# dcdr_3_1.net
KiCad netlist of a schematic drawn in EAGLE
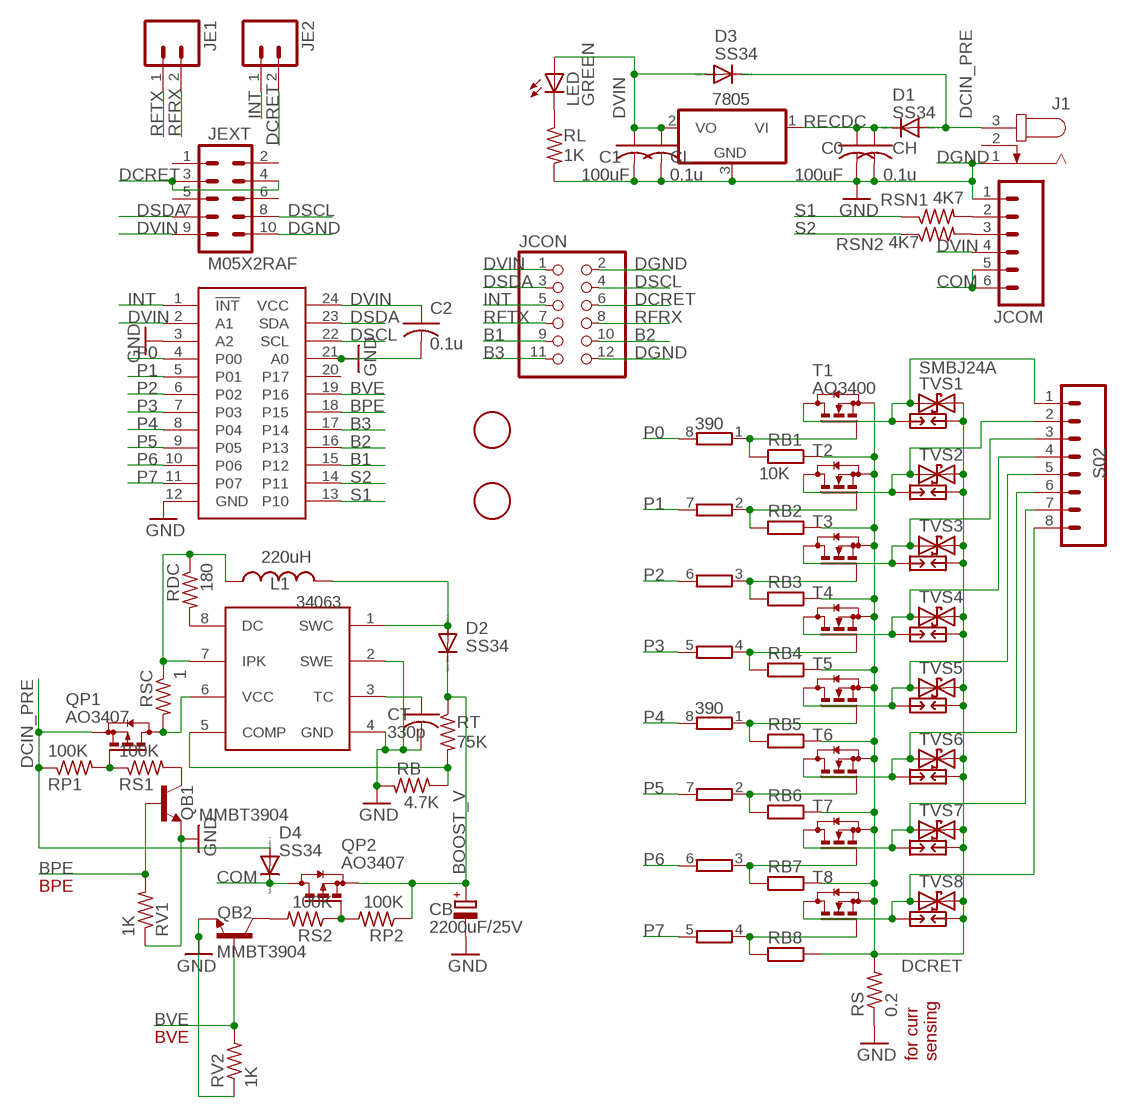
[diagram p0: schematic, sheet 1]

(export (version "E")
  (design (tool "Eeschema 10.0.6"))
  (components
    (comp (ref "7805")
      (value "7805DT")
      (footprint "eagle-import:TO252")
      (libsource (lib "eagle-import") (part "78DT05"))
    )
    (comp (ref "34063")
      (value "MC34063")
      (footprint "eagle-import:SO08")
      (libsource (lib "eagle-import") (part "MC33063/MC34063D"))
    )
    (comp (ref "C0")
      (value "100uF")
      (footprint "eagle-import:C0805K")
      (libsource (lib "eagle-import") (part "C-USC0805K"))
    )
    (comp (ref "C1")
      (value "100uF")
      (footprint "eagle-import:C0805K")
      (libsource (lib "eagle-import") (part "C-USC0805K"))
    )
    (comp (ref "C2")
      (value "0.1u")
      (footprint "eagle-import:C0603")
      (libsource (lib "eagle-import") (part "C-USC0603"))
    )
    (comp (ref "CB")
      (value "2200uF/25V")
      (footprint "eagle-import:E7,5-16")
      (libsource (lib "eagle-import") (part "CPOL-EUE7.5-16"))
    )
    (comp (ref "CH")
      (value "0.1u")
      (footprint "eagle-import:C0603")
      (libsource (lib "eagle-import") (part "C-USC0603"))
    )
    (comp (ref "CL")
      (value "0.1u")
      (footprint "eagle-import:C0603")
      (libsource (lib "eagle-import") (part "C-USC0603"))
    )
    (comp (ref "CT")
      (value "330p")
      (footprint "eagle-import:C0603K")
      (libsource (lib "eagle-import") (part "C-USC0603K"))
    )
    (comp (ref "D1")
      (value "SS34")
      (footprint "eagle-import:SMB")
      (libsource (lib "eagle-import") (part "DIODE-SMB"))
    )
    (comp (ref "D2")
      (value "SS34")
      (footprint "eagle-import:SMB")
      (libsource (lib "eagle-import") (part "DIODE-SMB"))
    )
    (comp (ref "D3")
      (value "SS34")
      (footprint "eagle-import:SMB")
      (libsource (lib "eagle-import") (part "DIODE-SMB"))
    )
    (comp (ref "D4")
      (value "SS34")
      (footprint "eagle-import:SMB")
      (libsource (lib "eagle-import") (part "DIODE-SMB"))
    )
    (comp (ref "J1")
      (value "JACK-PLUG0")
      (footprint "eagle-import:SPC4077")
      (libsource (lib "eagle-import") (part "JACK-PLUG0"))
    )
    (comp (ref "JCOM")
      (value "M065MM")
      (footprint "eagle-import:SCREWTERMINAL-5MM-6")
      (libsource (lib "eagle-import") (part "M065MM"))
    )
    (comp (ref "JCON")
      (value "PINHD-2X6")
      (footprint "eagle-import:2X06")
      (libsource (lib "eagle-import") (part "PINHD-2X6"))
    )
    (comp (ref "JE1")
      (value "M02PTH")
      (footprint "eagle-import:1X02")
      (libsource (lib "eagle-import") (part "M02PTH"))
    )
    (comp (ref "JE2")
      (value "M02PTH")
      (footprint "eagle-import:1X02")
      (libsource (lib "eagle-import") (part "M02PTH"))
    )
    (comp (ref "JEXT")
      (value "M05X2RAF")
      (footprint "eagle-import:2X5-RAF")
      (libsource (lib "eagle-import") (part "M05X2RAF"))
    )
    (comp (ref "L1")
      (value "220uH")
      (footprint "eagle-import:CR54")
      (libsource (lib "eagle-import") (part "INDUCTORCR54"))
    )
    (comp (ref "LED")
      (value "GREEN")
      (footprint "eagle-import:CHIPLED_0805")
      (libsource (lib "eagle-import") (part "LEDCHIPLED_0805"))
    )
    (comp (ref "PCA9555")
      (value "PCA9555")
      (footprint "eagle-import:TSSOP24")
      (libsource (lib "eagle-import") (part "PCF8575TSSOP24"))
    )
    (comp (ref "QB1")
      (value "MMBT3904")
      (footprint "eagle-import:SOT23-3")
      (libsource (lib "eagle-import") (part "TRANSISTOR_NPNSOT23-3"))
    )
    (comp (ref "QB2")
      (value "MMBT3904")
      (footprint "eagle-import:SOT23-3")
      (libsource (lib "eagle-import") (part "TRANSISTOR_NPNSOT23-3"))
    )
    (comp (ref "QP1")
      (value "AO3407")
      (footprint "eagle-import:SOT23")
      (libsource (lib "eagle-import") (part "BSS84"))
    )
    (comp (ref "QP2")
      (value "AO3407")
      (footprint "eagle-import:SOT23")
      (libsource (lib "eagle-import") (part "BSS84"))
    )
    (comp (ref "RB")
      (value "4.7K")
      (footprint "eagle-import:R0603")
      (libsource (lib "eagle-import") (part "adafruitGood_R-US_R0603"))
    )
    (comp (ref "RB1")
      (value "10K")
      (footprint "eagle-import:R0603")
      (libsource (lib "eagle-import") (part "R-EU_R0603"))
    )
    (comp (ref "RB2")
      (value "10K")
      (footprint "eagle-import:R0603")
      (libsource (lib "eagle-import") (part "R-EU_R0603"))
    )
    (comp (ref "RB3")
      (value "10K")
      (footprint "eagle-import:R0603")
      (libsource (lib "eagle-import") (part "R-EU_R0603"))
    )
    (comp (ref "RB4")
      (value "10K")
      (footprint "eagle-import:R0603")
      (libsource (lib "eagle-import") (part "R-EU_R0603"))
    )
    (comp (ref "RB5")
      (value "10K")
      (footprint "eagle-import:R0603")
      (libsource (lib "eagle-import") (part "R-EU_R0603"))
    )
    (comp (ref "RB6")
      (value "10K")
      (footprint "eagle-import:R0603")
      (libsource (lib "eagle-import") (part "R-EU_R0603"))
    )
    (comp (ref "RB7")
      (value "10K")
      (footprint "eagle-import:R0603")
      (libsource (lib "eagle-import") (part "R-EU_R0603"))
    )
    (comp (ref "RB8")
      (value "10K")
      (footprint "eagle-import:R0603")
      (libsource (lib "eagle-import") (part "R-EU_R0603"))
    )
    (comp (ref "RDC")
      (value "180")
      (footprint "eagle-import:R0603")
      (libsource (lib "eagle-import") (part "adafruitGood_R-US_R0603"))
    )
    (comp (ref "RL")
      (value "1K")
      (footprint "eagle-import:R0603")
      (libsource (lib "eagle-import") (part "adafruit2013_R-US_R0603"))
    )
    (comp (ref "RN1")
      (value "390")
      (footprint "eagle-import:EXB38V")
      (libsource (lib "eagle-import") (part "4R-NEXB38V"))
    )
    (comp (ref "RN2")
      (value "390")
      (footprint "eagle-import:EXB38V")
      (libsource (lib "eagle-import") (part "4R-NEXB38V"))
    )
    (comp (ref "RP1")
      (value "100K")
      (footprint "eagle-import:R0603")
      (libsource (lib "eagle-import") (part "adafruitGood_R-US_R0603"))
    )
    (comp (ref "RP2")
      (value "100K")
      (footprint "eagle-import:R0603")
      (libsource (lib "eagle-import") (part "adafruitGood_R-US_R0603"))
    )
    (comp (ref "RS")
      (value "0.2")
      (footprint "eagle-import:R2512")
      (libsource (lib "eagle-import") (part "R-US_R2512"))
    )
    (comp (ref "RS1")
      (value "100K")
      (footprint "eagle-import:R0603")
      (libsource (lib "eagle-import") (part "adafruitGood_R-US_R0603"))
    )
    (comp (ref "RS2")
      (value "100K")
      (footprint "eagle-import:R0603")
      (libsource (lib "eagle-import") (part "adafruitGood_R-US_R0603"))
    )
    (comp (ref "RSC")
      (value "1")
      (footprint "eagle-import:R0603")
      (libsource (lib "eagle-import") (part "adafruitGood_R-US_R0603"))
    )
    (comp (ref "RSN1")
      (value "4K7")
      (footprint "eagle-import:R0603")
      (libsource (lib "eagle-import") (part "adafruit2013_R-US_R0603"))
    )
    (comp (ref "RSN2")
      (value "4K7")
      (footprint "eagle-import:R0603")
      (libsource (lib "eagle-import") (part "adafruit2013_R-US_R0603"))
    )
    (comp (ref "RT")
      (value "75K")
      (footprint "eagle-import:R0603")
      (libsource (lib "eagle-import") (part "adafruitGood_R-US_R0603"))
    )
    (comp (ref "RV1")
      (value "1K")
      (footprint "eagle-import:R0603")
      (libsource (lib "eagle-import") (part "adafruitGood_R-US_R0603"))
    )
    (comp (ref "RV2")
      (value "1K")
      (footprint "eagle-import:R0603")
      (libsource (lib "eagle-import") (part "adafruitGood_R-US_R0603"))
    )
    (comp (ref "S02")
      (value "M085MM-8")
      (footprint "eagle-import:SCREWTERMINAL-5MM-8")
      (libsource (lib "eagle-import") (part "M085MM-8"))
    )
    (comp (ref "SP1")
      (value "PCB-SGAP")
      (footprint "eagle-import:PCB-SGAP")
      (libsource (lib "eagle-import") (part "PCB-SGAP"))
    )
    (comp (ref "SP2")
      (value "PCB-SGAP")
      (footprint "eagle-import:PCB-SGAP")
      (libsource (lib "eagle-import") (part "PCB-SGAP"))
    )
    (comp (ref "SP3")
      (value "PCB-SGAP")
      (footprint "eagle-import:PCB-SGAP")
      (libsource (lib "eagle-import") (part "PCB-SGAP"))
    )
    (comp (ref "SP4")
      (value "PCB-SGAP")
      (footprint "eagle-import:PCB-SGAP")
      (libsource (lib "eagle-import") (part "PCB-SGAP"))
    )
    (comp (ref "SP5")
      (value "PCB-SGAP")
      (footprint "eagle-import:PCB-SGAP")
      (libsource (lib "eagle-import") (part "PCB-SGAP"))
    )
    (comp (ref "SP6")
      (value "PCB-SGAP")
      (footprint "eagle-import:PCB-SGAP")
      (libsource (lib "eagle-import") (part "PCB-SGAP"))
    )
    (comp (ref "SP7")
      (value "PCB-SGAP")
      (footprint "eagle-import:PCB-SGAP")
      (libsource (lib "eagle-import") (part "PCB-SGAP"))
    )
    (comp (ref "SP8")
      (value "PCB-SGAP")
      (footprint "eagle-import:PCB-SGAP")
      (libsource (lib "eagle-import") (part "PCB-SGAP"))
    )
    (comp (ref "T1")
      (value "AO3400")
      (footprint "eagle-import:SOT23")
      (libsource (lib "eagle-import") (part "BSS123"))
    )
    (comp (ref "T2")
      (value "AO3400")
      (footprint "eagle-import:SOT23")
      (libsource (lib "eagle-import") (part "BSS123"))
    )
    (comp (ref "T3")
      (value "AO3400")
      (footprint "eagle-import:SOT23")
      (libsource (lib "eagle-import") (part "BSS123"))
    )
    (comp (ref "T4")
      (value "AO3400")
      (footprint "eagle-import:SOT23")
      (libsource (lib "eagle-import") (part "BSS123"))
    )
    (comp (ref "T5")
      (value "AO3400")
      (footprint "eagle-import:SOT23")
      (libsource (lib "eagle-import") (part "BSS123"))
    )
    (comp (ref "T6")
      (value "AO3400")
      (footprint "eagle-import:SOT23")
      (libsource (lib "eagle-import") (part "BSS123"))
    )
    (comp (ref "T7")
      (value "AO3400")
      (footprint "eagle-import:SOT23")
      (libsource (lib "eagle-import") (part "BSS123"))
    )
    (comp (ref "T8")
      (value "AO3400")
      (footprint "eagle-import:SOT23")
      (libsource (lib "eagle-import") (part "BSS123"))
    )
    (comp (ref "TVS1")
      (value "SMBJ24A")
      (footprint "eagle-import:SMB")
      (libsource (lib "eagle-import") (part "TVSSMB"))
    )
    (comp (ref "TVS2")
      (value "SMBJ24A")
      (footprint "eagle-import:SMB")
      (libsource (lib "eagle-import") (part "TVSSMB"))
    )
    (comp (ref "TVS3")
      (value "SMBJ24A")
      (footprint "eagle-import:SMB")
      (libsource (lib "eagle-import") (part "TVSSMB"))
    )
    (comp (ref "TVS4")
      (value "SMBJ24A")
      (footprint "eagle-import:SMB")
      (libsource (lib "eagle-import") (part "TVSSMB"))
    )
    (comp (ref "TVS5")
      (value "SMBJ24A")
      (footprint "eagle-import:SMB")
      (libsource (lib "eagle-import") (part "TVSSMB"))
    )
    (comp (ref "TVS6")
      (value "SMBJ24A")
      (footprint "eagle-import:SMB")
      (libsource (lib "eagle-import") (part "TVSSMB"))
    )
    (comp (ref "TVS7")
      (value "SMBJ24A")
      (footprint "eagle-import:SMB")
      (libsource (lib "eagle-import") (part "TVSSMB"))
    )
    (comp (ref "TVS8")
      (value "SMBJ24A")
      (footprint "eagle-import:SMB")
      (libsource (lib "eagle-import") (part "TVSSMB"))
    )
    (comp (ref "U$1")
      (value "FIDUCIAL")
      (footprint "eagle-import:FIDUCIAL_1MM")
      (libsource (lib "eagle-import") (part "FIDUCIAL"))
    )
    (comp (ref "U$2")
      (value "FIDUCIAL")
      (footprint "eagle-import:FIDUCIAL_1MM")
      (libsource (lib "eagle-import") (part "FIDUCIAL"))
    )
  )
  (nets
    (net (code "1") (name "/B1") (class "Default")
      (node (ref "JCON") (pin "9") (pinfunction "9_9") (pintype "passive"))
      (node (ref "PCA9555") (pin "15") (pinfunction "P12_15") (pintype "bidirectional"))
    )
    (net (code "2") (name "/B2") (class "Default")
      (node (ref "JCON") (pin "10") (pinfunction "10_10") (pintype "passive"))
      (node (ref "PCA9555") (pin "16") (pinfunction "P13_16") (pintype "bidirectional"))
    )
    (net (code "3") (name "/B3") (class "Default")
      (node (ref "JCON") (pin "11") (pinfunction "11_11") (pintype "passive"))
      (node (ref "PCA9555") (pin "17") (pinfunction "P14_17") (pintype "bidirectional"))
    )
    (net (code "4") (name "/BOOST_V") (class "Default")
      (node (ref "CB") (pin "+") (pinfunction "+_+") (pintype "passive"))
      (node (ref "D2") (pin "C") (pinfunction "C_C") (pintype "passive"))
      (node (ref "QP2") (pin "2") (pinfunction "S_2") (pintype "passive"))
      (node (ref "RP2") (pin "1") (pinfunction "1_1") (pintype "passive"))
      (node (ref "RT") (pin "1") (pinfunction "1_1") (pintype "passive"))
    )
    (net (code "5") (name "/BPE") (class "Default")
      (node (ref "PCA9555") (pin "18") (pinfunction "P15_18") (pintype "bidirectional"))
      (node (ref "QB1") (pin "1") (pinfunction "B_1") (pintype "passive"))
      (node (ref "RV1") (pin "2") (pinfunction "2_2") (pintype "passive"))
    )
    (net (code "6") (name "/BVE") (class "Default")
      (node (ref "PCA9555") (pin "19") (pinfunction "P16_19") (pintype "bidirectional"))
      (node (ref "QB2") (pin "1") (pinfunction "B_1") (pintype "passive"))
      (node (ref "RV2") (pin "2") (pinfunction "2_2") (pintype "passive"))
    )
    (net (code "7") (name "/COM") (class "Default")
      (node (ref "D4") (pin "C") (pinfunction "C_C") (pintype "passive"))
      (node (ref "JCOM") (pin "5") (pinfunction "5_5") (pintype "passive"))
      (node (ref "JCOM") (pin "6") (pinfunction "6_6") (pintype "passive"))
      (node (ref "QP2") (pin "3") (pinfunction "D_3") (pintype "passive"))
    )
    (net (code "8") (name "/DCIN_PRE") (class "Default")
      (node (ref "D1") (pin "A") (pinfunction "A_A") (pintype "passive"))
      (node (ref "D3") (pin "C") (pinfunction "C_C") (pintype "passive"))
      (node (ref "D4") (pin "A") (pinfunction "A_A") (pintype "passive"))
      (node (ref "J1") (pin "3") (pinfunction "3_3") (pintype "passive"))
      (node (ref "QP1") (pin "2") (pinfunction "S_2") (pintype "passive"))
      (node (ref "RP1") (pin "1") (pinfunction "1_1") (pintype "passive"))
    )
    (net (code "9") (name "/DCRET") (class "Default")
      (node (ref "JCON") (pin "6") (pinfunction "6_6") (pintype "passive"))
      (node (ref "JE2") (pin "2") (pinfunction "2_2") (pintype "passive"))
      (node (ref "JEXT") (pin "3") (pinfunction "3_3") (pintype "passive"))
      (node (ref "JEXT") (pin "4") (pinfunction "4_4") (pintype "passive"))
      (node (ref "RB1") (pin "1") (pinfunction "1_1") (pintype "passive"))
      (node (ref "RB2") (pin "1") (pinfunction "1_1") (pintype "passive"))
      (node (ref "RB3") (pin "1") (pinfunction "1_1") (pintype "passive"))
      (node (ref "RB4") (pin "1") (pinfunction "1_1") (pintype "passive"))
      (node (ref "RB5") (pin "1") (pinfunction "1_1") (pintype "passive"))
      (node (ref "RB6") (pin "1") (pinfunction "1_1") (pintype "passive"))
      (node (ref "RB7") (pin "1") (pinfunction "1_1") (pintype "passive"))
      (node (ref "RB8") (pin "1") (pinfunction "1_1") (pintype "passive"))
      (node (ref "RS") (pin "2") (pinfunction "2_2") (pintype "passive"))
      (node (ref "SP1") (pin "1") (pinfunction "1_1") (pintype "passive"))
      (node (ref "SP2") (pin "1") (pinfunction "1_1") (pintype "passive"))
      (node (ref "SP3") (pin "1") (pinfunction "1_1") (pintype "passive"))
      (node (ref "SP4") (pin "1") (pinfunction "1_1") (pintype "passive"))
      (node (ref "SP5") (pin "1") (pinfunction "1_1") (pintype "passive"))
      (node (ref "SP6") (pin "1") (pinfunction "1_1") (pintype "passive"))
      (node (ref "SP7") (pin "1") (pinfunction "1_1") (pintype "passive"))
      (node (ref "SP8") (pin "1") (pinfunction "1_1") (pintype "passive"))
      (node (ref "T1") (pin "2") (pinfunction "S_2") (pintype "passive"))
      (node (ref "T2") (pin "2") (pinfunction "S_2") (pintype "passive"))
      (node (ref "T3") (pin "2") (pinfunction "S_2") (pintype "passive"))
      (node (ref "T4") (pin "2") (pinfunction "S_2") (pintype "passive"))
      (node (ref "T5") (pin "2") (pinfunction "S_2") (pintype "passive"))
      (node (ref "T6") (pin "2") (pinfunction "S_2") (pintype "passive"))
      (node (ref "T7") (pin "2") (pinfunction "S_2") (pintype "passive"))
      (node (ref "T8") (pin "2") (pinfunction "S_2") (pintype "passive"))
      (node (ref "TVS1") (pin "C") (pinfunction "C_C") (pintype "passive"))
      (node (ref "TVS2") (pin "C") (pinfunction "C_C") (pintype "passive"))
      (node (ref "TVS3") (pin "C") (pinfunction "C_C") (pintype "passive"))
      (node (ref "TVS4") (pin "C") (pinfunction "C_C") (pintype "passive"))
      (node (ref "TVS5") (pin "C") (pinfunction "C_C") (pintype "passive"))
      (node (ref "TVS6") (pin "C") (pinfunction "C_C") (pintype "passive"))
      (node (ref "TVS7") (pin "C") (pinfunction "C_C") (pintype "passive"))
      (node (ref "TVS8") (pin "C") (pinfunction "C_C") (pintype "passive"))
    )
    (net (code "10") (name "/DSCL") (class "Default")
      (node (ref "JCON") (pin "4") (pinfunction "4_4") (pintype "passive"))
      (node (ref "JEXT") (pin "8") (pinfunction "8_8") (pintype "passive"))
      (node (ref "PCA9555") (pin "22") (pinfunction "SCL_22") (pintype "bidirectional"))
    )
    (net (code "11") (name "/DSDA") (class "Default")
      (node (ref "JCON") (pin "3") (pinfunction "3_3") (pintype "passive"))
      (node (ref "JEXT") (pin "7") (pinfunction "7_7") (pintype "passive"))
      (node (ref "PCA9555") (pin "23") (pinfunction "SDA_23") (pintype "bidirectional"))
    )
    (net (code "12") (name "/DVIN") (class "Default")
      (node (ref "7805") (pin "2") (pinfunction "VO_2") (pintype "passive"))
      (node (ref "C1") (pin "1") (pinfunction "1_1") (pintype "passive"))
      (node (ref "C2") (pin "1") (pinfunction "1_1") (pintype "passive"))
      (node (ref "CL") (pin "1") (pinfunction "1_1") (pintype "passive"))
      (node (ref "D3") (pin "A") (pinfunction "A_A") (pintype "passive"))
      (node (ref "JCOM") (pin "4") (pinfunction "4_4") (pintype "passive"))
      (node (ref "JCON") (pin "1") (pinfunction "1_1") (pintype "passive"))
      (node (ref "JEXT") (pin "9") (pinfunction "9_9") (pintype "passive"))
      (node (ref "LED") (pin "A") (pinfunction "A_A") (pintype "passive"))
      (node (ref "PCA9555") (pin "2") (pinfunction "A1_2") (pintype "bidirectional"))
      (node (ref "PCA9555") (pin "24") (pinfunction "VCC_24") (pintype "power_in"))
    )
    (net (code "13") (name "/INT") (class "Default")
      (node (ref "JCON") (pin "5") (pinfunction "5_5") (pintype "passive"))
      (node (ref "JE2") (pin "1") (pinfunction "1_1") (pintype "passive"))
      (node (ref "PCA9555") (pin "1") (pinfunction "~{INT}_1") (pintype "bidirectional"))
    )
    (net (code "14") (name "/P0") (class "Default")
      (node (ref "PCA9555") (pin "4") (pinfunction "P00_4") (pintype "bidirectional"))
      (node (ref "RN1") (pin "8") (pinfunction "2_8") (pintype "passive"))
    )
    (net (code "15") (name "/P1") (class "Default")
      (node (ref "PCA9555") (pin "5") (pinfunction "P01_5") (pintype "bidirectional"))
      (node (ref "RN1") (pin "7") (pinfunction "2_7") (pintype "passive"))
    )
    (net (code "16") (name "/P2") (class "Default")
      (node (ref "PCA9555") (pin "6") (pinfunction "P02_6") (pintype "bidirectional"))
      (node (ref "RN1") (pin "6") (pinfunction "2_6") (pintype "passive"))
    )
    (net (code "17") (name "/P3") (class "Default")
      (node (ref "PCA9555") (pin "7") (pinfunction "P03_7") (pintype "bidirectional"))
      (node (ref "RN1") (pin "5") (pinfunction "2_5") (pintype "passive"))
    )
    (net (code "18") (name "/P4") (class "Default")
      (node (ref "PCA9555") (pin "8") (pinfunction "P04_8") (pintype "bidirectional"))
      (node (ref "RN2") (pin "8") (pinfunction "2_8") (pintype "passive"))
    )
    (net (code "19") (name "/P5") (class "Default")
      (node (ref "PCA9555") (pin "9") (pinfunction "P05_9") (pintype "bidirectional"))
      (node (ref "RN2") (pin "7") (pinfunction "2_7") (pintype "passive"))
    )
    (net (code "20") (name "/P6") (class "Default")
      (node (ref "PCA9555") (pin "10") (pinfunction "P06_10") (pintype "bidirectional"))
      (node (ref "RN2") (pin "6") (pinfunction "2_6") (pintype "passive"))
    )
    (net (code "21") (name "/P7") (class "Default")
      (node (ref "PCA9555") (pin "11") (pinfunction "P07_11") (pintype "bidirectional"))
      (node (ref "RN2") (pin "5") (pinfunction "2_5") (pintype "passive"))
    )
    (net (code "22") (name "/RECDC") (class "Default")
      (node (ref "7805") (pin "1") (pinfunction "VI_1") (pintype "input"))
      (node (ref "C0") (pin "1") (pinfunction "1_1") (pintype "passive"))
      (node (ref "CH") (pin "1") (pinfunction "1_1") (pintype "passive"))
      (node (ref "D1") (pin "C") (pinfunction "C_C") (pintype "passive"))
    )
    (net (code "23") (name "/RFRX") (class "Default")
      (node (ref "JCON") (pin "8") (pinfunction "8_8") (pintype "passive"))
      (node (ref "JE1") (pin "2") (pinfunction "2_2") (pintype "passive"))
    )
    (net (code "24") (name "/RFTX") (class "Default")
      (node (ref "JCON") (pin "7") (pinfunction "7_7") (pintype "passive"))
      (node (ref "JE1") (pin "1") (pinfunction "1_1") (pintype "passive"))
    )
    (net (code "25") (name "/S1") (class "Default")
      (node (ref "PCA9555") (pin "13") (pinfunction "P10_13") (pintype "bidirectional"))
      (node (ref "RSN1") (pin "1") (pinfunction "1_1") (pintype "passive"))
    )
    (net (code "26") (name "/S2") (class "Default")
      (node (ref "PCA9555") (pin "14") (pinfunction "P11_14") (pintype "bidirectional"))
      (node (ref "RSN2") (pin "1") (pinfunction "1_1") (pintype "passive"))
    )
    (net (code "27") (name "GND") (class "Default")
      (node (ref "34063") (pin "2") (pinfunction "SWE_2") (pintype "input"))
      (node (ref "34063") (pin "4") (pinfunction "GND_4") (pintype "power_in"))
      (node (ref "7805") (pin "3") (pinfunction "GND_3") (pintype "passive"))
      (node (ref "C0") (pin "2") (pinfunction "2_2") (pintype "passive"))
      (node (ref "C1") (pin "2") (pinfunction "2_2") (pintype "passive"))
      (node (ref "C2") (pin "2") (pinfunction "2_2") (pintype "passive"))
      (node (ref "CB") (pin "-") (pinfunction "-_-") (pintype "passive"))
      (node (ref "CH") (pin "2") (pinfunction "2_2") (pintype "passive"))
      (node (ref "CL") (pin "2") (pinfunction "2_2") (pintype "passive"))
      (node (ref "CT") (pin "2") (pinfunction "2_2") (pintype "passive"))
      (node (ref "J1") (pin "1") (pinfunction "1_1") (pintype "passive"))
      (node (ref "JCOM") (pin "1") (pinfunction "1_1") (pintype "passive"))
      (node (ref "JCON") (pin "12") (pinfunction "12_12") (pintype "passive"))
      (node (ref "JCON") (pin "2") (pinfunction "2_2") (pintype "passive"))
      (node (ref "JEXT") (pin "10") (pinfunction "10_10") (pintype "passive"))
      (node (ref "PCA9555") (pin "12") (pinfunction "GND_12") (pintype "power_in"))
      (node (ref "PCA9555") (pin "21") (pinfunction "A0_21") (pintype "bidirectional"))
      (node (ref "PCA9555") (pin "3") (pinfunction "A2_3") (pintype "bidirectional"))
      (node (ref "QB1") (pin "2") (pinfunction "E_2") (pintype "passive"))
      (node (ref "QB2") (pin "2") (pinfunction "E_2") (pintype "passive"))
      (node (ref "RB") (pin "2") (pinfunction "2_2") (pintype "passive"))
      (node (ref "RL") (pin "2") (pinfunction "2_2") (pintype "passive"))
      (node (ref "RS") (pin "1") (pinfunction "1_1") (pintype "passive"))
      (node (ref "RV1") (pin "1") (pinfunction "1_1") (pintype "passive"))
      (node (ref "RV2") (pin "1") (pinfunction "1_1") (pintype "passive"))
    )
    (net (code "28") (name "Net-(34063-COMP)") (class "Default")
      (node (ref "34063") (pin "5") (pinfunction "COMP_5") (pintype "input"))
      (node (ref "RB") (pin "1") (pinfunction "1_1") (pintype "passive"))
      (node (ref "RT") (pin "2") (pinfunction "2_2") (pintype "passive"))
    )
    (net (code "29") (name "Net-(34063-DC)") (class "Default")
      (node (ref "34063") (pin "8") (pinfunction "DC_8") (pintype "input"))
      (node (ref "RDC") (pin "2") (pinfunction "2_2") (pintype "passive"))
    )
    (net (code "30") (name "Net-(34063-IPK)") (class "Default")
      (node (ref "34063") (pin "7") (pinfunction "IPK_7") (pintype "bidirectional"))
      (node (ref "L1") (pin "P$1") (pinfunction "1_P$1") (pintype "passive"))
      (node (ref "RDC") (pin "1") (pinfunction "1_1") (pintype "passive"))
      (node (ref "RSC") (pin "1") (pinfunction "1_1") (pintype "passive"))
    )
    (net (code "31") (name "Net-(34063-SWC)") (class "Default")
      (node (ref "34063") (pin "1") (pinfunction "SWC_1") (pintype "input"))
      (node (ref "D2") (pin "A") (pinfunction "A_A") (pintype "passive"))
      (node (ref "L1") (pin "P$2") (pinfunction "2_P$2") (pintype "passive"))
    )
    (net (code "32") (name "Net-(34063-TC)") (class "Default")
      (node (ref "34063") (pin "3") (pinfunction "TC_3") (pintype "input"))
      (node (ref "CT") (pin "1") (pinfunction "1_1") (pintype "passive"))
    )
    (net (code "33") (name "Net-(34063-VCC)") (class "Default")
      (node (ref "34063") (pin "6") (pinfunction "VCC_6") (pintype "power_in"))
      (node (ref "QP1") (pin "3") (pinfunction "D_3") (pintype "passive"))
      (node (ref "RSC") (pin "2") (pinfunction "2_2") (pintype "passive"))
    )
    (net (code "34") (name "Net-(JCOM-Pad2)") (class "Default")
      (node (ref "JCOM") (pin "2") (pinfunction "2_2") (pintype "passive"))
      (node (ref "RSN1") (pin "2") (pinfunction "2_2") (pintype "passive"))
    )
    (net (code "35") (name "Net-(JCOM-Pad3)") (class "Default")
      (node (ref "JCOM") (pin "3") (pinfunction "3_3") (pintype "passive"))
      (node (ref "RSN2") (pin "2") (pinfunction "2_2") (pintype "passive"))
    )
    (net (code "36") (name "Net-(LED-PadC)") (class "Default")
      (node (ref "LED") (pin "C") (pinfunction "C_C") (pintype "passive"))
      (node (ref "RL") (pin "1") (pinfunction "1_1") (pintype "passive"))
    )
    (net (code "37") (name "Net-(QB1-C)") (class "Default")
      (node (ref "QB1") (pin "3") (pinfunction "C_3") (pintype "passive"))
      (node (ref "RS1") (pin "2") (pinfunction "2_2") (pintype "passive"))
    )
    (net (code "38") (name "Net-(QB2-C)") (class "Default")
      (node (ref "QB2") (pin "3") (pinfunction "C_3") (pintype "passive"))
      (node (ref "RS2") (pin "2") (pinfunction "2_2") (pintype "passive"))
    )
    (net (code "39") (name "Net-(QP1-G)") (class "Default")
      (node (ref "QP1") (pin "1") (pinfunction "G_1") (pintype "passive"))
      (node (ref "RP1") (pin "2") (pinfunction "2_2") (pintype "passive"))
      (node (ref "RS1") (pin "1") (pinfunction "1_1") (pintype "passive"))
    )
    (net (code "40") (name "Net-(QP2-G)") (class "Default")
      (node (ref "QP2") (pin "1") (pinfunction "G_1") (pintype "passive"))
      (node (ref "RP2") (pin "2") (pinfunction "2_2") (pintype "passive"))
      (node (ref "RS2") (pin "1") (pinfunction "1_1") (pintype "passive"))
    )
    (net (code "41") (name "Net-(RN1B-1)") (class "Default")
      (node (ref "RB2") (pin "2") (pinfunction "2_2") (pintype "passive"))
      (node (ref "RN1") (pin "2") (pinfunction "1_2") (pintype "passive"))
      (node (ref "T2") (pin "1") (pinfunction "G_1") (pintype "passive"))
    )
    (net (code "42") (name "Net-(RN1C-1)") (class "Default")
      (node (ref "RB3") (pin "2") (pinfunction "2_2") (pintype "passive"))
      (node (ref "RN1") (pin "3") (pinfunction "1_3") (pintype "passive"))
      (node (ref "T3") (pin "1") (pinfunction "G_1") (pintype "passive"))
    )
    (net (code "43") (name "Net-(RN1D-1)") (class "Default")
      (node (ref "RB4") (pin "2") (pinfunction "2_2") (pintype "passive"))
      (node (ref "RN1") (pin "4") (pinfunction "1_4") (pintype "passive"))
      (node (ref "T4") (pin "1") (pinfunction "G_1") (pintype "passive"))
    )
    (net (code "44") (name "Net-(RN2B-1)") (class "Default")
      (node (ref "RB6") (pin "2") (pinfunction "2_2") (pintype "passive"))
      (node (ref "RN2") (pin "2") (pinfunction "1_2") (pintype "passive"))
      (node (ref "T6") (pin "1") (pinfunction "G_1") (pintype "passive"))
    )
    (net (code "45") (name "Net-(RN2C-1)") (class "Default")
      (node (ref "RB7") (pin "2") (pinfunction "2_2") (pintype "passive"))
      (node (ref "RN2") (pin "3") (pinfunction "1_3") (pintype "passive"))
      (node (ref "T7") (pin "1") (pinfunction "G_1") (pintype "passive"))
    )
    (net (code "46") (name "Net-(RN2D-1)") (class "Default")
      (node (ref "RB8") (pin "2") (pinfunction "2_2") (pintype "passive"))
      (node (ref "RN2") (pin "4") (pinfunction "1_4") (pintype "passive"))
      (node (ref "T8") (pin "1") (pinfunction "G_1") (pintype "passive"))
    )
    (net (code "47") (name "Net-(T1-D)") (class "Default")
      (node (ref "S02") (pin "1") (pinfunction "1_1") (pintype "passive"))
      (node (ref "SP1") (pin "2") (pinfunction "2_2") (pintype "passive"))
      (node (ref "T1") (pin "3") (pinfunction "D_3") (pintype "passive"))
      (node (ref "TVS1") (pin "A") (pinfunction "A_A") (pintype "passive"))
    )
    (net (code "48") (name "Net-(T1-G)") (class "Default")
      (node (ref "RB1") (pin "2") (pinfunction "2_2") (pintype "passive"))
      (node (ref "RN1") (pin "1") (pinfunction "1_1") (pintype "passive"))
      (node (ref "T1") (pin "1") (pinfunction "G_1") (pintype "passive"))
    )
    (net (code "49") (name "Net-(T2-D)") (class "Default")
      (node (ref "S02") (pin "2") (pinfunction "2_2") (pintype "passive"))
      (node (ref "SP2") (pin "2") (pinfunction "2_2") (pintype "passive"))
      (node (ref "T2") (pin "3") (pinfunction "D_3") (pintype "passive"))
      (node (ref "TVS2") (pin "A") (pinfunction "A_A") (pintype "passive"))
    )
    (net (code "50") (name "Net-(T3-D)") (class "Default")
      (node (ref "S02") (pin "3") (pinfunction "3_3") (pintype "passive"))
      (node (ref "SP3") (pin "2") (pinfunction "2_2") (pintype "passive"))
      (node (ref "T3") (pin "3") (pinfunction "D_3") (pintype "passive"))
      (node (ref "TVS3") (pin "A") (pinfunction "A_A") (pintype "passive"))
    )
    (net (code "51") (name "Net-(T4-D)") (class "Default")
      (node (ref "S02") (pin "4") (pinfunction "4_4") (pintype "passive"))
      (node (ref "SP4") (pin "2") (pinfunction "2_2") (pintype "passive"))
      (node (ref "T4") (pin "3") (pinfunction "D_3") (pintype "passive"))
      (node (ref "TVS4") (pin "A") (pinfunction "A_A") (pintype "passive"))
    )
    (net (code "52") (name "Net-(T5-D)") (class "Default")
      (node (ref "S02") (pin "5") (pinfunction "5_5") (pintype "passive"))
      (node (ref "SP5") (pin "2") (pinfunction "2_2") (pintype "passive"))
      (node (ref "T5") (pin "3") (pinfunction "D_3") (pintype "passive"))
      (node (ref "TVS5") (pin "A") (pinfunction "A_A") (pintype "passive"))
    )
    (net (code "53") (name "Net-(T5-G)") (class "Default")
      (node (ref "RB5") (pin "2") (pinfunction "2_2") (pintype "passive"))
      (node (ref "RN2") (pin "1") (pinfunction "1_1") (pintype "passive"))
      (node (ref "T5") (pin "1") (pinfunction "G_1") (pintype "passive"))
    )
    (net (code "54") (name "Net-(T6-D)") (class "Default")
      (node (ref "S02") (pin "6") (pinfunction "6_6") (pintype "passive"))
      (node (ref "SP6") (pin "2") (pinfunction "2_2") (pintype "passive"))
      (node (ref "T6") (pin "3") (pinfunction "D_3") (pintype "passive"))
      (node (ref "TVS6") (pin "A") (pinfunction "A_A") (pintype "passive"))
    )
    (net (code "55") (name "Net-(T7-D)") (class "Default")
      (node (ref "S02") (pin "7") (pinfunction "7_7") (pintype "passive"))
      (node (ref "SP7") (pin "2") (pinfunction "2_2") (pintype "passive"))
      (node (ref "T7") (pin "3") (pinfunction "D_3") (pintype "passive"))
      (node (ref "TVS7") (pin "A") (pinfunction "A_A") (pintype "passive"))
    )
    (net (code "56") (name "Net-(T8-D)") (class "Default")
      (node (ref "S02") (pin "8") (pinfunction "8_8") (pintype "passive"))
      (node (ref "SP8") (pin "2") (pinfunction "2_2") (pintype "passive"))
      (node (ref "T8") (pin "3") (pinfunction "D_3") (pintype "passive"))
      (node (ref "TVS8") (pin "A") (pinfunction "A_A") (pintype "passive"))
    )
    (net (code "57") (name "unconnected-(J1-Pad2)") (class "Default")
      (node (ref "J1") (pin "2") (pinfunction "2_2") (pintype "passive"))
    )
    (net (code "58") (name "unconnected-(JEXT-Pad1)") (class "Default")
      (node (ref "JEXT") (pin "1") (pinfunction "1_1") (pintype "passive"))
    )
    (net (code "59") (name "unconnected-(JEXT-Pad2)") (class "Default")
      (node (ref "JEXT") (pin "2") (pinfunction "2_2") (pintype "passive"))
    )
    (net (code "60") (name "unconnected-(JEXT-Pad5)") (class "Default")
      (node (ref "JEXT") (pin "5") (pinfunction "5_5") (pintype "passive"))
    )
    (net (code "61") (name "unconnected-(JEXT-Pad6)") (class "Default")
      (node (ref "JEXT") (pin "6") (pinfunction "6_6") (pintype "passive"))
    )
    (net (code "62") (name "unconnected-(PCA9555-P17-Pad20)") (class "Default")
      (node (ref "PCA9555") (pin "20") (pinfunction "P17_20") (pintype "bidirectional"))
    )
  )
)
